# unoedge.net
KiCad netlist of a schematic drawn in EAGLE
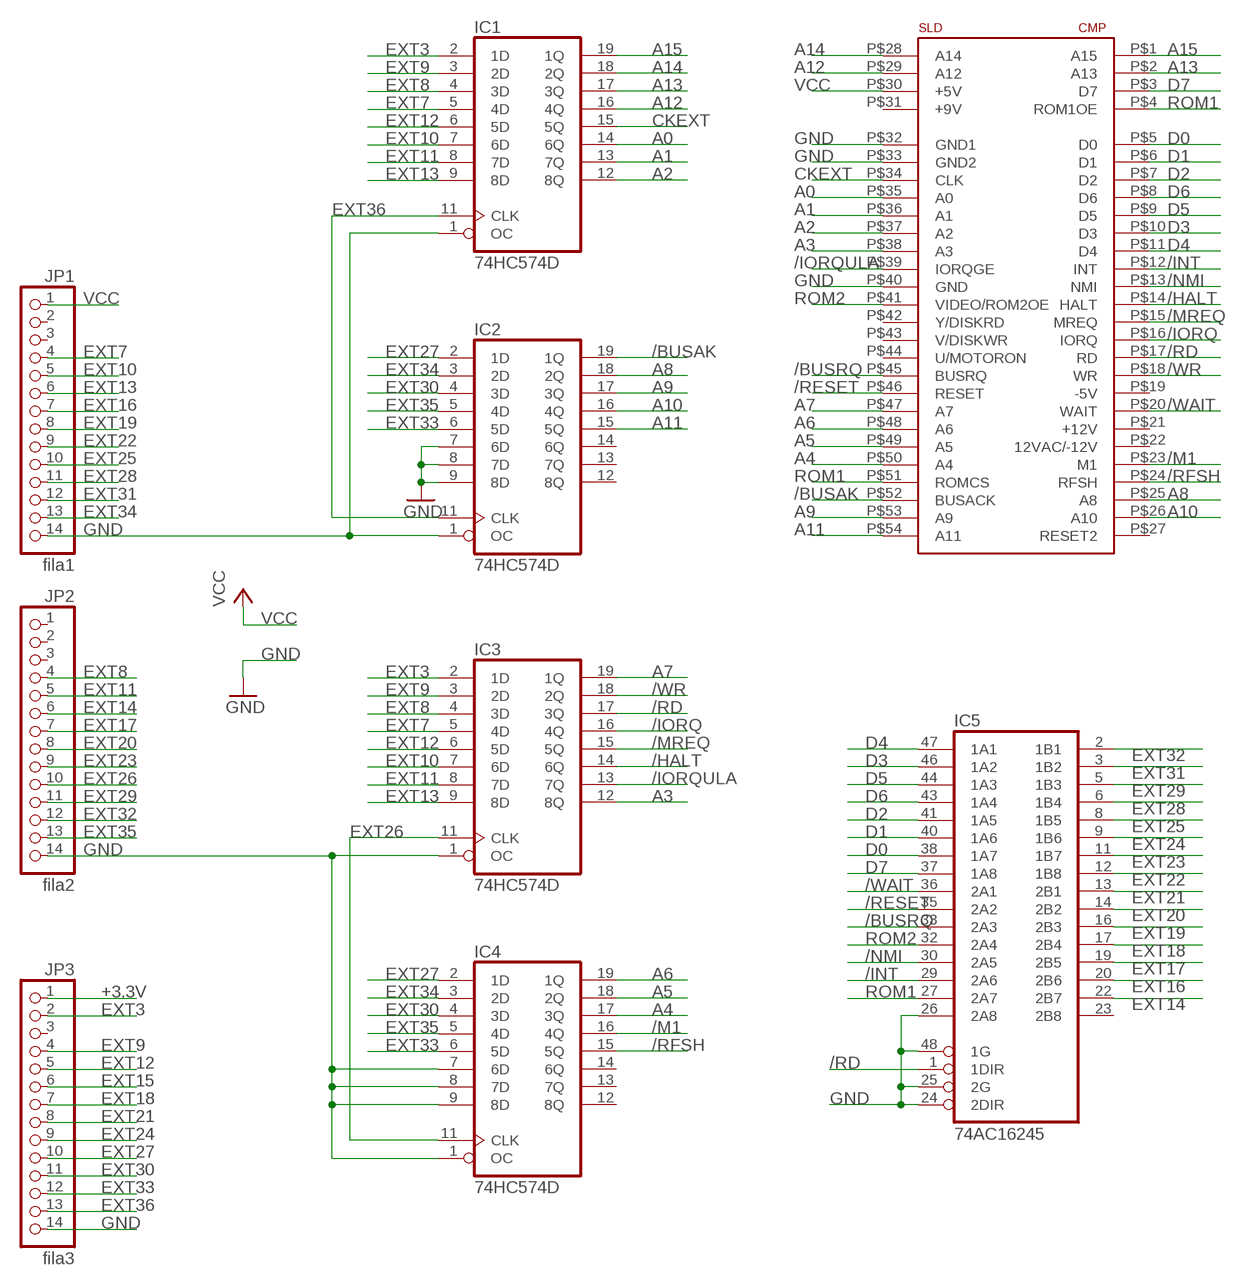
[diagram p0: schematic, sheet 1]

(export (version "E")
  (design (tool "Eeschema 10.0.6"))
  (components
    (comp (ref "IC1")
      (value "74HC574D")
      (footprint "eagle-import:SO20W")
      (libsource (lib "eagle-import") (part "74574DHC"))
    )
    (comp (ref "IC2")
      (value "74HC574D")
      (footprint "eagle-import:SO20W")
      (libsource (lib "eagle-import") (part "74574DHC"))
    )
    (comp (ref "IC3")
      (value "74HC574D")
      (footprint "eagle-import:SO20W")
      (libsource (lib "eagle-import") (part "74574DHC"))
    )
    (comp (ref "IC4")
      (value "74HC574D")
      (footprint "eagle-import:SO20W")
      (libsource (lib "eagle-import") (part "74574DHC"))
    )
    (comp (ref "IC5")
      (value "74AC16245")
      (footprint "eagle-import:SSOP48DL")
      (libsource (lib "eagle-import") (part "74AC16245"))
    )
    (comp (ref "JP1")
      (value "fila1")
      (footprint "eagle-import:1X14")
      (libsource (lib "eagle-import") (part "PINHD-1X14"))
    )
    (comp (ref "JP2")
      (value "fila2")
      (footprint "eagle-import:1X14")
      (libsource (lib "eagle-import") (part "PINHD-1X14"))
    )
    (comp (ref "JP3")
      (value "fila3")
      (footprint "eagle-import:1X14")
      (libsource (lib "eagle-import") (part "PINHD-1X14"))
    )
    (comp (ref "U$2")
      (value "CONECTOR_EDGE_LADO_SPECTRUM")
      (footprint "eagle-import:CONECTOR_LADO_SPECTRUM")
      (libsource (lib "eagle-import") (part "CONECTOR_EDGE_LADO_SPECTRUM"))
    )
  )
  (nets
    (net (code "1") (name "/+3.3V") (class "Default")
      (node (ref "JP3") (pin "1") (pinfunction "1_1") (pintype "passive"))
    )
    (net (code "2") (name "/A0") (class "Default")
      (node (ref "IC1") (pin "14") (pinfunction "6Q_14") (pintype "tri_state"))
      (node (ref "U$2") (pin "P$35") (pinfunction "A0_P$35") (pintype "bidirectional"))
    )
    (net (code "3") (name "/A1") (class "Default")
      (node (ref "IC1") (pin "13") (pinfunction "7Q_13") (pintype "tri_state"))
      (node (ref "U$2") (pin "P$36") (pinfunction "A1_P$36") (pintype "bidirectional"))
    )
    (net (code "4") (name "/A2") (class "Default")
      (node (ref "IC1") (pin "12") (pinfunction "8Q_12") (pintype "tri_state"))
      (node (ref "U$2") (pin "P$37") (pinfunction "A2_P$37") (pintype "bidirectional"))
    )
    (net (code "5") (name "/A3") (class "Default")
      (node (ref "IC3") (pin "12") (pinfunction "8Q_12") (pintype "tri_state"))
      (node (ref "U$2") (pin "P$38") (pinfunction "A3_P$38") (pintype "bidirectional"))
    )
    (net (code "6") (name "/A4") (class "Default")
      (node (ref "IC4") (pin "17") (pinfunction "3Q_17") (pintype "tri_state"))
      (node (ref "U$2") (pin "P$50") (pinfunction "A4_P$50") (pintype "bidirectional"))
    )
    (net (code "7") (name "/A5") (class "Default")
      (node (ref "IC4") (pin "18") (pinfunction "2Q_18") (pintype "tri_state"))
      (node (ref "U$2") (pin "P$49") (pinfunction "A5_P$49") (pintype "bidirectional"))
    )
    (net (code "8") (name "/A6") (class "Default")
      (node (ref "IC4") (pin "19") (pinfunction "1Q_19") (pintype "tri_state"))
      (node (ref "U$2") (pin "P$48") (pinfunction "A6_P$48") (pintype "bidirectional"))
    )
    (net (code "9") (name "/A7") (class "Default")
      (node (ref "IC3") (pin "19") (pinfunction "1Q_19") (pintype "tri_state"))
      (node (ref "U$2") (pin "P$47") (pinfunction "A7_P$47") (pintype "bidirectional"))
    )
    (net (code "10") (name "/A8") (class "Default")
      (node (ref "IC2") (pin "18") (pinfunction "2Q_18") (pintype "tri_state"))
      (node (ref "U$2") (pin "P$25") (pinfunction "A8_P$25") (pintype "bidirectional"))
    )
    (net (code "11") (name "/A9") (class "Default")
      (node (ref "IC2") (pin "17") (pinfunction "3Q_17") (pintype "tri_state"))
      (node (ref "U$2") (pin "P$53") (pinfunction "A9_P$53") (pintype "bidirectional"))
    )
    (net (code "12") (name "/A10") (class "Default")
      (node (ref "IC2") (pin "16") (pinfunction "4Q_16") (pintype "tri_state"))
      (node (ref "U$2") (pin "P$26") (pinfunction "A10_P$26") (pintype "bidirectional"))
    )
    (net (code "13") (name "/A11") (class "Default")
      (node (ref "IC2") (pin "15") (pinfunction "5Q_15") (pintype "tri_state"))
      (node (ref "U$2") (pin "P$54") (pinfunction "A11_P$54") (pintype "bidirectional"))
    )
    (net (code "14") (name "/A12") (class "Default")
      (node (ref "IC1") (pin "16") (pinfunction "4Q_16") (pintype "tri_state"))
      (node (ref "U$2") (pin "P$29") (pinfunction "A12_P$29") (pintype "bidirectional"))
    )
    (net (code "15") (name "/A13") (class "Default")
      (node (ref "IC1") (pin "17") (pinfunction "3Q_17") (pintype "tri_state"))
      (node (ref "U$2") (pin "P$2") (pinfunction "A13_P$2") (pintype "bidirectional"))
    )
    (net (code "16") (name "/A14") (class "Default")
      (node (ref "IC1") (pin "18") (pinfunction "2Q_18") (pintype "tri_state"))
      (node (ref "U$2") (pin "P$28") (pinfunction "A14_P$28") (pintype "bidirectional"))
    )
    (net (code "17") (name "/A15") (class "Default")
      (node (ref "IC1") (pin "19") (pinfunction "1Q_19") (pintype "tri_state"))
      (node (ref "U$2") (pin "P$1") (pinfunction "A15_P$1") (pintype "bidirectional"))
    )
    (net (code "18") (name "/CKEXT") (class "Default")
      (node (ref "IC1") (pin "15") (pinfunction "5Q_15") (pintype "tri_state"))
      (node (ref "U$2") (pin "P$34") (pinfunction "CLK_P$34") (pintype "bidirectional"))
    )
    (net (code "19") (name "/D0") (class "Default")
      (node (ref "IC5") (pin "38") (pinfunction "1A7_38") (pintype "bidirectional"))
      (node (ref "U$2") (pin "P$5") (pinfunction "D0_P$5") (pintype "bidirectional"))
    )
    (net (code "20") (name "/D1") (class "Default")
      (node (ref "IC5") (pin "40") (pinfunction "1A6_40") (pintype "bidirectional"))
      (node (ref "U$2") (pin "P$6") (pinfunction "D1_P$6") (pintype "bidirectional"))
    )
    (net (code "21") (name "/D2") (class "Default")
      (node (ref "IC5") (pin "41") (pinfunction "1A5_41") (pintype "bidirectional"))
      (node (ref "U$2") (pin "P$7") (pinfunction "D2_P$7") (pintype "bidirectional"))
    )
    (net (code "22") (name "/D3") (class "Default")
      (node (ref "IC5") (pin "46") (pinfunction "1A2_46") (pintype "bidirectional"))
      (node (ref "U$2") (pin "P$10") (pinfunction "D3_P$10") (pintype "bidirectional"))
    )
    (net (code "23") (name "/D4") (class "Default")
      (node (ref "IC5") (pin "47") (pinfunction "1A1_47") (pintype "bidirectional"))
      (node (ref "U$2") (pin "P$11") (pinfunction "D4_P$11") (pintype "bidirectional"))
    )
    (net (code "24") (name "/D5") (class "Default")
      (node (ref "IC5") (pin "44") (pinfunction "1A3_44") (pintype "bidirectional"))
      (node (ref "U$2") (pin "P$9") (pinfunction "D5_P$9") (pintype "bidirectional"))
    )
    (net (code "25") (name "/D6") (class "Default")
      (node (ref "IC5") (pin "43") (pinfunction "1A4_43") (pintype "bidirectional"))
      (node (ref "U$2") (pin "P$8") (pinfunction "D6_P$8") (pintype "bidirectional"))
    )
    (net (code "26") (name "/D7") (class "Default")
      (node (ref "IC5") (pin "37") (pinfunction "1A8_37") (pintype "bidirectional"))
      (node (ref "U$2") (pin "P$3") (pinfunction "D7_P$3") (pintype "bidirectional"))
    )
    (net (code "27") (name "/EXT3") (class "Default")
      (node (ref "IC1") (pin "2") (pinfunction "1D_2") (pintype "input"))
      (node (ref "IC3") (pin "2") (pinfunction "1D_2") (pintype "input"))
      (node (ref "JP3") (pin "2") (pinfunction "2_2") (pintype "passive"))
    )
    (net (code "28") (name "/EXT7") (class "Default")
      (node (ref "IC1") (pin "5") (pinfunction "4D_5") (pintype "input"))
      (node (ref "IC3") (pin "5") (pinfunction "4D_5") (pintype "input"))
      (node (ref "JP1") (pin "4") (pinfunction "4_4") (pintype "passive"))
    )
    (net (code "29") (name "/EXT8") (class "Default")
      (node (ref "IC1") (pin "4") (pinfunction "3D_4") (pintype "input"))
      (node (ref "IC3") (pin "4") (pinfunction "3D_4") (pintype "input"))
      (node (ref "JP2") (pin "4") (pinfunction "4_4") (pintype "passive"))
    )
    (net (code "30") (name "/EXT9") (class "Default")
      (node (ref "IC1") (pin "3") (pinfunction "2D_3") (pintype "input"))
      (node (ref "IC3") (pin "3") (pinfunction "2D_3") (pintype "input"))
      (node (ref "JP3") (pin "4") (pinfunction "4_4") (pintype "passive"))
    )
    (net (code "31") (name "/EXT10") (class "Default")
      (node (ref "IC1") (pin "7") (pinfunction "6D_7") (pintype "input"))
      (node (ref "IC3") (pin "7") (pinfunction "6D_7") (pintype "input"))
      (node (ref "JP1") (pin "5") (pinfunction "5_5") (pintype "passive"))
    )
    (net (code "32") (name "/EXT11") (class "Default")
      (node (ref "IC1") (pin "8") (pinfunction "7D_8") (pintype "input"))
      (node (ref "IC3") (pin "8") (pinfunction "7D_8") (pintype "input"))
      (node (ref "JP2") (pin "5") (pinfunction "5_5") (pintype "passive"))
    )
    (net (code "33") (name "/EXT12") (class "Default")
      (node (ref "IC1") (pin "6") (pinfunction "5D_6") (pintype "input"))
      (node (ref "IC3") (pin "6") (pinfunction "5D_6") (pintype "input"))
      (node (ref "JP3") (pin "5") (pinfunction "5_5") (pintype "passive"))
    )
    (net (code "34") (name "/EXT13") (class "Default")
      (node (ref "IC1") (pin "9") (pinfunction "8D_9") (pintype "input"))
      (node (ref "IC3") (pin "9") (pinfunction "8D_9") (pintype "input"))
      (node (ref "JP1") (pin "6") (pinfunction "6_6") (pintype "passive"))
    )
    (net (code "35") (name "/EXT14") (class "Default")
      (node (ref "IC5") (pin "22") (pinfunction "2B7_22") (pintype "bidirectional"))
      (node (ref "JP2") (pin "6") (pinfunction "6_6") (pintype "passive"))
    )
    (net (code "36") (name "/EXT15") (class "Default")
      (node (ref "JP3") (pin "6") (pinfunction "6_6") (pintype "passive"))
    )
    (net (code "37") (name "/EXT16") (class "Default")
      (node (ref "IC5") (pin "20") (pinfunction "2B6_20") (pintype "bidirectional"))
      (node (ref "JP1") (pin "7") (pinfunction "7_7") (pintype "passive"))
    )
    (net (code "38") (name "/EXT17") (class "Default")
      (node (ref "IC5") (pin "19") (pinfunction "2B5_19") (pintype "bidirectional"))
      (node (ref "JP2") (pin "7") (pinfunction "7_7") (pintype "passive"))
    )
    (net (code "39") (name "/EXT18") (class "Default")
      (node (ref "IC5") (pin "17") (pinfunction "2B4_17") (pintype "bidirectional"))
      (node (ref "JP3") (pin "7") (pinfunction "7_7") (pintype "passive"))
    )
    (net (code "40") (name "/EXT19") (class "Default")
      (node (ref "IC5") (pin "16") (pinfunction "2B3_16") (pintype "bidirectional"))
      (node (ref "JP1") (pin "8") (pinfunction "8_8") (pintype "passive"))
    )
    (net (code "41") (name "/EXT20") (class "Default")
      (node (ref "IC5") (pin "14") (pinfunction "2B2_14") (pintype "bidirectional"))
      (node (ref "JP2") (pin "8") (pinfunction "8_8") (pintype "passive"))
    )
    (net (code "42") (name "/EXT21") (class "Default")
      (node (ref "IC5") (pin "13") (pinfunction "2B1_13") (pintype "bidirectional"))
      (node (ref "JP3") (pin "8") (pinfunction "8_8") (pintype "passive"))
    )
    (net (code "43") (name "/EXT22") (class "Default")
      (node (ref "IC5") (pin "12") (pinfunction "1B8_12") (pintype "bidirectional"))
      (node (ref "JP1") (pin "9") (pinfunction "9_9") (pintype "passive"))
    )
    (net (code "44") (name "/EXT23") (class "Default")
      (node (ref "IC5") (pin "11") (pinfunction "1B7_11") (pintype "bidirectional"))
      (node (ref "JP2") (pin "9") (pinfunction "9_9") (pintype "passive"))
    )
    (net (code "45") (name "/EXT24") (class "Default")
      (node (ref "IC5") (pin "9") (pinfunction "1B6_9") (pintype "bidirectional"))
      (node (ref "JP3") (pin "9") (pinfunction "9_9") (pintype "passive"))
    )
    (net (code "46") (name "/EXT25") (class "Default")
      (node (ref "IC5") (pin "8") (pinfunction "1B5_8") (pintype "bidirectional"))
      (node (ref "JP1") (pin "10") (pinfunction "10_10") (pintype "passive"))
    )
    (net (code "47") (name "/EXT26") (class "Default")
      (node (ref "IC3") (pin "11") (pinfunction "CLK_11") (pintype "input"))
      (node (ref "IC4") (pin "11") (pinfunction "CLK_11") (pintype "input"))
      (node (ref "JP2") (pin "10") (pinfunction "10_10") (pintype "passive"))
    )
    (net (code "48") (name "/EXT27") (class "Default")
      (node (ref "IC2") (pin "2") (pinfunction "1D_2") (pintype "input"))
      (node (ref "IC4") (pin "2") (pinfunction "1D_2") (pintype "input"))
      (node (ref "JP3") (pin "10") (pinfunction "10_10") (pintype "passive"))
    )
    (net (code "49") (name "/EXT28") (class "Default")
      (node (ref "IC5") (pin "6") (pinfunction "1B4_6") (pintype "bidirectional"))
      (node (ref "JP1") (pin "11") (pinfunction "11_11") (pintype "passive"))
    )
    (net (code "50") (name "/EXT29") (class "Default")
      (node (ref "IC5") (pin "5") (pinfunction "1B3_5") (pintype "bidirectional"))
      (node (ref "JP2") (pin "11") (pinfunction "11_11") (pintype "passive"))
    )
    (net (code "51") (name "/EXT30") (class "Default")
      (node (ref "IC2") (pin "4") (pinfunction "3D_4") (pintype "input"))
      (node (ref "IC4") (pin "4") (pinfunction "3D_4") (pintype "input"))
      (node (ref "JP3") (pin "11") (pinfunction "11_11") (pintype "passive"))
    )
    (net (code "52") (name "/EXT31") (class "Default")
      (node (ref "IC5") (pin "3") (pinfunction "1B2_3") (pintype "bidirectional"))
      (node (ref "JP1") (pin "12") (pinfunction "12_12") (pintype "passive"))
    )
    (net (code "53") (name "/EXT32") (class "Default")
      (node (ref "IC5") (pin "2") (pinfunction "1B1_2") (pintype "bidirectional"))
      (node (ref "JP2") (pin "12") (pinfunction "12_12") (pintype "passive"))
    )
    (net (code "54") (name "/EXT33") (class "Default")
      (node (ref "IC2") (pin "6") (pinfunction "5D_6") (pintype "input"))
      (node (ref "IC4") (pin "6") (pinfunction "5D_6") (pintype "input"))
      (node (ref "JP3") (pin "12") (pinfunction "12_12") (pintype "passive"))
    )
    (net (code "55") (name "/EXT34") (class "Default")
      (node (ref "IC2") (pin "3") (pinfunction "2D_3") (pintype "input"))
      (node (ref "IC4") (pin "3") (pinfunction "2D_3") (pintype "input"))
      (node (ref "JP1") (pin "13") (pinfunction "13_13") (pintype "passive"))
    )
    (net (code "56") (name "/EXT35") (class "Default")
      (node (ref "IC2") (pin "5") (pinfunction "4D_5") (pintype "input"))
      (node (ref "IC4") (pin "5") (pinfunction "4D_5") (pintype "input"))
      (node (ref "JP2") (pin "13") (pinfunction "13_13") (pintype "passive"))
    )
    (net (code "57") (name "/EXT36") (class "Default")
      (node (ref "IC1") (pin "11") (pinfunction "CLK_11") (pintype "input"))
      (node (ref "IC2") (pin "11") (pinfunction "CLK_11") (pintype "input"))
      (node (ref "JP3") (pin "13") (pinfunction "13_13") (pintype "passive"))
    )
    (net (code "58") (name "/ROM1") (class "Default")
      (node (ref "IC5") (pin "27") (pinfunction "2A7_27") (pintype "bidirectional"))
      (node (ref "U$2") (pin "P$4") (pinfunction "ROM1OE_P$4") (pintype "bidirectional"))
      (node (ref "U$2") (pin "P$51") (pinfunction "ROMCS_P$51") (pintype "bidirectional"))
    )
    (net (code "59") (name "/ROM2") (class "Default")
      (node (ref "IC5") (pin "32") (pinfunction "2A4_32") (pintype "bidirectional"))
      (node (ref "U$2") (pin "P$41") (pinfunction "VIDEO/ROM2OE_P$41") (pintype "bidirectional"))
    )
    (net (code "60") (name "/{slash}BUSAK") (class "Default")
      (node (ref "IC2") (pin "19") (pinfunction "1Q_19") (pintype "tri_state"))
      (node (ref "U$2") (pin "P$52") (pinfunction "BUSACK_P$52") (pintype "bidirectional"))
    )
    (net (code "61") (name "/{slash}BUSRQ") (class "Default")
      (node (ref "IC5") (pin "33") (pinfunction "2A3_33") (pintype "bidirectional"))
      (node (ref "U$2") (pin "P$45") (pinfunction "BUSRQ_P$45") (pintype "bidirectional"))
    )
    (net (code "62") (name "/{slash}HALT") (class "Default")
      (node (ref "IC3") (pin "14") (pinfunction "6Q_14") (pintype "tri_state"))
      (node (ref "U$2") (pin "P$14") (pinfunction "HALT_P$14") (pintype "bidirectional"))
    )
    (net (code "63") (name "/{slash}INT") (class "Default")
      (node (ref "IC5") (pin "29") (pinfunction "2A6_29") (pintype "bidirectional"))
      (node (ref "U$2") (pin "P$12") (pinfunction "INT_P$12") (pintype "bidirectional"))
    )
    (net (code "64") (name "/{slash}IORQ") (class "Default")
      (node (ref "IC3") (pin "16") (pinfunction "4Q_16") (pintype "tri_state"))
      (node (ref "U$2") (pin "P$16") (pinfunction "IORQ_P$16") (pintype "bidirectional"))
    )
    (net (code "65") (name "/{slash}IORQULA") (class "Default")
      (node (ref "IC3") (pin "13") (pinfunction "7Q_13") (pintype "tri_state"))
      (node (ref "U$2") (pin "P$39") (pinfunction "IORQGE_P$39") (pintype "bidirectional"))
    )
    (net (code "66") (name "/{slash}M1") (class "Default")
      (node (ref "IC4") (pin "16") (pinfunction "4Q_16") (pintype "tri_state"))
      (node (ref "U$2") (pin "P$23") (pinfunction "M1_P$23") (pintype "bidirectional"))
    )
    (net (code "67") (name "/{slash}MREQ") (class "Default")
      (node (ref "IC3") (pin "15") (pinfunction "5Q_15") (pintype "tri_state"))
      (node (ref "U$2") (pin "P$15") (pinfunction "MREQ_P$15") (pintype "bidirectional"))
    )
    (net (code "68") (name "/{slash}NMI") (class "Default")
      (node (ref "IC5") (pin "30") (pinfunction "2A5_30") (pintype "bidirectional"))
      (node (ref "U$2") (pin "P$13") (pinfunction "NMI_P$13") (pintype "bidirectional"))
    )
    (net (code "69") (name "/{slash}RD") (class "Default")
      (node (ref "IC3") (pin "17") (pinfunction "3Q_17") (pintype "tri_state"))
      (node (ref "IC5") (pin "1") (pinfunction "1DIR_1") (pintype "input"))
      (node (ref "U$2") (pin "P$17") (pinfunction "RD_P$17") (pintype "bidirectional"))
    )
    (net (code "70") (name "/{slash}RESET") (class "Default")
      (node (ref "IC5") (pin "35") (pinfunction "2A2_35") (pintype "bidirectional"))
      (node (ref "U$2") (pin "P$46") (pinfunction "RESET_P$46") (pintype "bidirectional"))
    )
    (net (code "71") (name "/{slash}RFSH") (class "Default")
      (node (ref "IC4") (pin "15") (pinfunction "5Q_15") (pintype "tri_state"))
      (node (ref "U$2") (pin "P$24") (pinfunction "RFSH_P$24") (pintype "bidirectional"))
    )
    (net (code "72") (name "/{slash}WAIT") (class "Default")
      (node (ref "IC5") (pin "36") (pinfunction "2A1_36") (pintype "bidirectional"))
      (node (ref "U$2") (pin "P$20") (pinfunction "WAIT_P$20") (pintype "bidirectional"))
    )
    (net (code "73") (name "/{slash}WR") (class "Default")
      (node (ref "IC3") (pin "18") (pinfunction "2Q_18") (pintype "tri_state"))
      (node (ref "U$2") (pin "P$18") (pinfunction "WR_P$18") (pintype "bidirectional"))
    )
    (net (code "74") (name "GND") (class "Default")
      (node (ref "IC1") (pin "1") (pinfunction "OC_1") (pintype "input"))
      (node (ref "IC2") (pin "1") (pinfunction "OC_1") (pintype "input"))
      (node (ref "IC2") (pin "7") (pinfunction "6D_7") (pintype "input"))
      (node (ref "IC2") (pin "8") (pinfunction "7D_8") (pintype "input"))
      (node (ref "IC2") (pin "9") (pinfunction "8D_9") (pintype "input"))
      (node (ref "IC3") (pin "1") (pinfunction "OC_1") (pintype "input"))
      (node (ref "IC4") (pin "1") (pinfunction "OC_1") (pintype "input"))
      (node (ref "IC4") (pin "7") (pinfunction "6D_7") (pintype "input"))
      (node (ref "IC4") (pin "8") (pinfunction "7D_8") (pintype "input"))
      (node (ref "IC4") (pin "9") (pinfunction "8D_9") (pintype "input"))
      (node (ref "IC5") (pin "24") (pinfunction "2DIR_24") (pintype "input"))
      (node (ref "IC5") (pin "25") (pinfunction "2G_25") (pintype "input"))
      (node (ref "IC5") (pin "26") (pinfunction "2A8_26") (pintype "bidirectional"))
      (node (ref "IC5") (pin "48") (pinfunction "1G_48") (pintype "input"))
      (node (ref "JP1") (pin "14") (pinfunction "14_14") (pintype "passive"))
      (node (ref "JP2") (pin "14") (pinfunction "14_14") (pintype "passive"))
      (node (ref "JP3") (pin "14") (pinfunction "14_14") (pintype "passive"))
      (node (ref "U$2") (pin "P$32") (pinfunction "GND1_P$32") (pintype "bidirectional"))
      (node (ref "U$2") (pin "P$33") (pinfunction "GND2_P$33") (pintype "bidirectional"))
      (node (ref "U$2") (pin "P$40") (pinfunction "GND_P$40") (pintype "bidirectional"))
    )
    (net (code "75") (name "VCC") (class "Default")
      (node (ref "JP1") (pin "1") (pinfunction "1_1") (pintype "passive"))
      (node (ref "U$2") (pin "P$30") (pinfunction "+5V_P$30") (pintype "bidirectional"))
    )
    (net (code "76") (name "unconnected-(IC2A-6Q-Pad14)") (class "Default")
      (node (ref "IC2") (pin "14") (pinfunction "6Q_14") (pintype "tri_state"))
    )
    (net (code "77") (name "unconnected-(IC2A-7Q-Pad13)") (class "Default")
      (node (ref "IC2") (pin "13") (pinfunction "7Q_13") (pintype "tri_state"))
    )
    (net (code "78") (name "unconnected-(IC2A-8Q-Pad12)") (class "Default")
      (node (ref "IC2") (pin "12") (pinfunction "8Q_12") (pintype "tri_state"))
    )
    (net (code "79") (name "unconnected-(IC4A-6Q-Pad14)") (class "Default")
      (node (ref "IC4") (pin "14") (pinfunction "6Q_14") (pintype "tri_state"))
    )
    (net (code "80") (name "unconnected-(IC4A-7Q-Pad13)") (class "Default")
      (node (ref "IC4") (pin "13") (pinfunction "7Q_13") (pintype "tri_state"))
    )
    (net (code "81") (name "unconnected-(IC4A-8Q-Pad12)") (class "Default")
      (node (ref "IC4") (pin "12") (pinfunction "8Q_12") (pintype "tri_state"))
    )
    (net (code "82") (name "unconnected-(IC5A-2B8-Pad23)") (class "Default")
      (node (ref "IC5") (pin "23") (pinfunction "2B8_23") (pintype "bidirectional"))
    )
    (net (code "83") (name "unconnected-(JP1-Pad2)") (class "Default")
      (node (ref "JP1") (pin "2") (pinfunction "2_2") (pintype "passive"))
    )
    (net (code "84") (name "unconnected-(JP1-Pad3)") (class "Default")
      (node (ref "JP1") (pin "3") (pinfunction "3_3") (pintype "passive"))
    )
    (net (code "85") (name "unconnected-(JP2-Pad1)") (class "Default")
      (node (ref "JP2") (pin "1") (pinfunction "1_1") (pintype "passive"))
    )
    (net (code "86") (name "unconnected-(JP2-Pad2)") (class "Default")
      (node (ref "JP2") (pin "2") (pinfunction "2_2") (pintype "passive"))
    )
    (net (code "87") (name "unconnected-(JP2-Pad3)") (class "Default")
      (node (ref "JP2") (pin "3") (pinfunction "3_3") (pintype "passive"))
    )
    (net (code "88") (name "unconnected-(JP3-Pad3)") (class "Default")
      (node (ref "JP3") (pin "3") (pinfunction "3_3") (pintype "passive"))
    )
    (net (code "89") (name "unconnected-(U$2-+9V-PadP$31)") (class "Default")
      (node (ref "U$2") (pin "P$31") (pinfunction "+9V_P$31") (pintype "bidirectional"))
    )
    (net (code "90") (name "unconnected-(U$2-+12V-PadP$21)") (class "Default")
      (node (ref "U$2") (pin "P$21") (pinfunction "+12V_P$21") (pintype "bidirectional"))
    )
    (net (code "91") (name "unconnected-(U$2--5V-PadP$19)") (class "Default")
      (node (ref "U$2") (pin "P$19") (pinfunction "-5V_P$19") (pintype "bidirectional"))
    )
    (net (code "92") (name "unconnected-(U$2-12VAC{slash}-12V-PadP$22)") (class "Default")
      (node (ref "U$2") (pin "P$22") (pinfunction "12VAC/-12V_P$22") (pintype "bidirectional"))
    )
    (net (code "93") (name "unconnected-(U$2-RESET2-PadP$27)") (class "Default")
      (node (ref "U$2") (pin "P$27") (pinfunction "RESET2_P$27") (pintype "bidirectional"))
    )
    (net (code "94") (name "unconnected-(U$2-U{slash}MOTORON-PadP$44)") (class "Default")
      (node (ref "U$2") (pin "P$44") (pinfunction "U/MOTORON_P$44") (pintype "bidirectional"))
    )
    (net (code "95") (name "unconnected-(U$2-V{slash}DISKWR-PadP$43)") (class "Default")
      (node (ref "U$2") (pin "P$43") (pinfunction "V/DISKWR_P$43") (pintype "bidirectional"))
    )
    (net (code "96") (name "unconnected-(U$2-Y{slash}DISKRD-PadP$42)") (class "Default")
      (node (ref "U$2") (pin "P$42") (pinfunction "Y/DISKRD_P$42") (pintype "bidirectional"))
    )
  )
)
